# Latch_IMD.net
KiCad netlist of a schematic drawn in Altium Designer
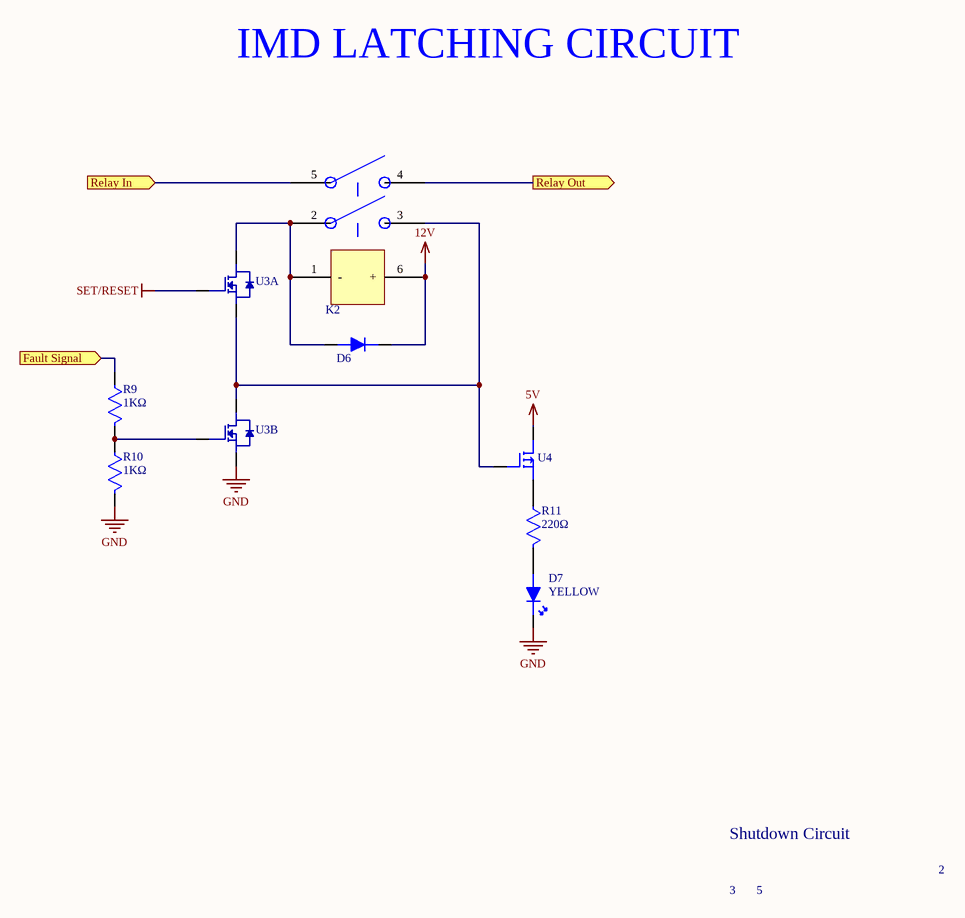
[diagram p0: Latch_IMD.SchDoc]

(export (version "E")
  (design (tool "Eeschema 10.0.6"))
  (components
    (comp (ref "D6")
      (value "SD560BTR")
      (footprint "DIODE")
      (description "DIODE GEN PURP 600V 5A SMB")
      (fields (field (name "MANUFACTURER") "SMC"))
      (libsource (lib "sdc_prech_schlib") (part "SD560BTR"))
    )
    (comp (ref "D7")
      (value "YELLOW")
      (footprint "LED 0603")
      (description "LED YELLOW CLEAR SMD")
      (fields
        (field (name "MANUFACTURER") "Vishay Lite-On")
        (field (name "MANUFACTURER PART NUMBER") "LTST-C191KSKT")
      )
      (libsource (lib "sdc_prech_schlib") (part "LTST-C191KSKT"))
    )
    (comp (ref "K2")
      (value "5-1419124-6")
      (footprint "RELAY DPST SDC")
      (description "General Purpose Relay, Osa Series, Power, Non Latching, Dpst-No, 12 Vdc, 3 A Rohs Compliant: Yes")
      (fields (field (name "MANUFACTURER") "TE Connectivity"))
      (libsource (lib "sdc_prech_schlib") (part "5-1419124-6"))
    )
    (comp (ref "R9")
      (value "1KΩ")
      (footprint "RESISTOR 0603")
      (description "RES SMD 220 OHM 5% 1/10W 0603")
      (fields
        (field (name "MANUFACTURER") "Vishay")
        (field (name "MANUFACTURER PART NUMBER") "CRCW0603220RJNEA")
      )
      (libsource (lib "sdc_prech_schlib") (part "CRCW0603220RJNEA"))
    )
    (comp (ref "R10")
      (value "1KΩ")
      (footprint "RESISTOR 0603")
      (description "RES SMD 220 OHM 5% 1/10W 0603")
      (fields
        (field (name "MANUFACTURER") "Vishay")
        (field (name "MANUFACTURER PART NUMBER") "CRCW0603220RJNEA")
      )
      (libsource (lib "sdc_prech_schlib") (part "CRCW0603220RJNEA"))
    )
    (comp (ref "R11")
      (value "220Ω")
      (footprint "RESISTOR 0603")
      (description "RES SMD 220 OHM 5% 1/10W 0603")
      (fields
        (field (name "MANUFACTURER") "Vishay")
        (field (name "MANUFACTURER PART NUMBER") "CRCW0603220RJNEA")
      )
      (libsource (lib "sdc_prech_schlib") (part "CRCW0603220RJNEA"))
    )
    (comp (ref "U3")
      (value "SSM6N7002CFU,LF")
      (footprint "N-MOSFET (2 FETS)")
      (description "MOSFET 2N-CH 60V 0.17A US6")
      (fields (field (name "MANUFACTURER") "Toshiba"))
      (libsource (lib "sdc_prech_schlib") (part "SSM6N7002CFU,LF"))
    )
    (comp (ref "U4")
      (value "NTD2955T4GOSCT-ND")
      (footprint "DPAK-TO252")
      (description "MOSFET P-CH 60V 12A DPAK")
      (fields
        (field (name "MANUFACTURER") "ON Semiconductor")
        (field (name "MANUFACTURER PART NUMBER") "NTD2955T4G")
      )
      (libsource (lib "Transistors") (part "P-FET-60V-12A"))
    )
  )
  (nets
    (net (code "1") (name "/Fault Signal") (class "Default")
      (node (ref "R9") (pin "1") (pinfunction "1_1") (pintype "passive"))
    )
    (net (code "2") (name "/Relay In") (class "Default") (node (ref "K2") (pin "5") (pintype "passive")))
    (net (code "3") (name "/Relay Out") (class "Default") (node (ref "K2") (pin "4") (pintype "passive")))
    (net (code "4") (name "5V") (class "Default")
      (node (ref "U4") (pin "2") (pinfunction "2_2") (pintype "passive"))
    )
    (net (code "5") (name "12V") (class "Default")
      (node (ref "D6") (pin "2") (pinfunction "2_2") (pintype "passive"))
      (node (ref "K2") (pin "6") (pinfunction "+_6") (pintype "passive"))
    )
    (net (code "6") (name "GND") (class "Default")
      (node (ref "D7") (pin "2") (pinfunction "2_2") (pintype "passive"))
      (node (ref "R10") (pin "2") (pinfunction "2_2") (pintype "passive"))
      (node (ref "U3") (pin "4") (pinfunction "S2_4") (pintype "passive"))
    )
    (net (code "7") (name "Net-(D7-Pad1)") (class "Default")
      (node (ref "D7") (pin "1") (pinfunction "1_1") (pintype "passive"))
      (node (ref "R11") (pin "2") (pinfunction "2_2") (pintype "passive"))
    )
    (net (code "8") (name "Net-(K2--)") (class "Default")
      (node (ref "D6") (pin "1") (pinfunction "1_1") (pintype "passive"))
      (node (ref "K2") (pin "1") (pinfunction "-_1") (pintype "passive"))
      (node (ref "K2") (pin "2") (pintype "passive"))
      (node (ref "U3") (pin "6") (pinfunction "D1_6") (pintype "passive"))
    )
    (net (code "9") (name "Net-(R11-Pad1)") (class "Default")
      (node (ref "R11") (pin "1") (pinfunction "1_1") (pintype "passive"))
      (node (ref "U4") (pin "3") (pinfunction "3_3") (pintype "passive"))
    )
    (net (code "10") (name "Net-(U3A-S1)") (class "Default")
      (node (ref "K2") (pin "3") (pintype "passive"))
      (node (ref "U3") (pin "1") (pinfunction "S1_1") (pintype "passive"))
      (node (ref "U3") (pin "3") (pinfunction "D2_3") (pintype "passive"))
      (node (ref "U4") (pin "1") (pinfunction "1_1") (pintype "passive"))
    )
    (net (code "11") (name "Net-(U3B-G2)") (class "Default")
      (node (ref "R10") (pin "1") (pinfunction "1_1") (pintype "passive"))
      (node (ref "R9") (pin "2") (pinfunction "2_2") (pintype "passive"))
      (node (ref "U3") (pin "5") (pinfunction "G2_5") (pintype "passive"))
    )
    (net (code "12") (name "SET{slash}RESET") (class "Default")
      (node (ref "U3") (pin "2") (pinfunction "G1_2") (pintype "passive"))
    )
  )
)
